# CurrentSensor.net
KiCad netlist of a schematic drawn in Altium Designer
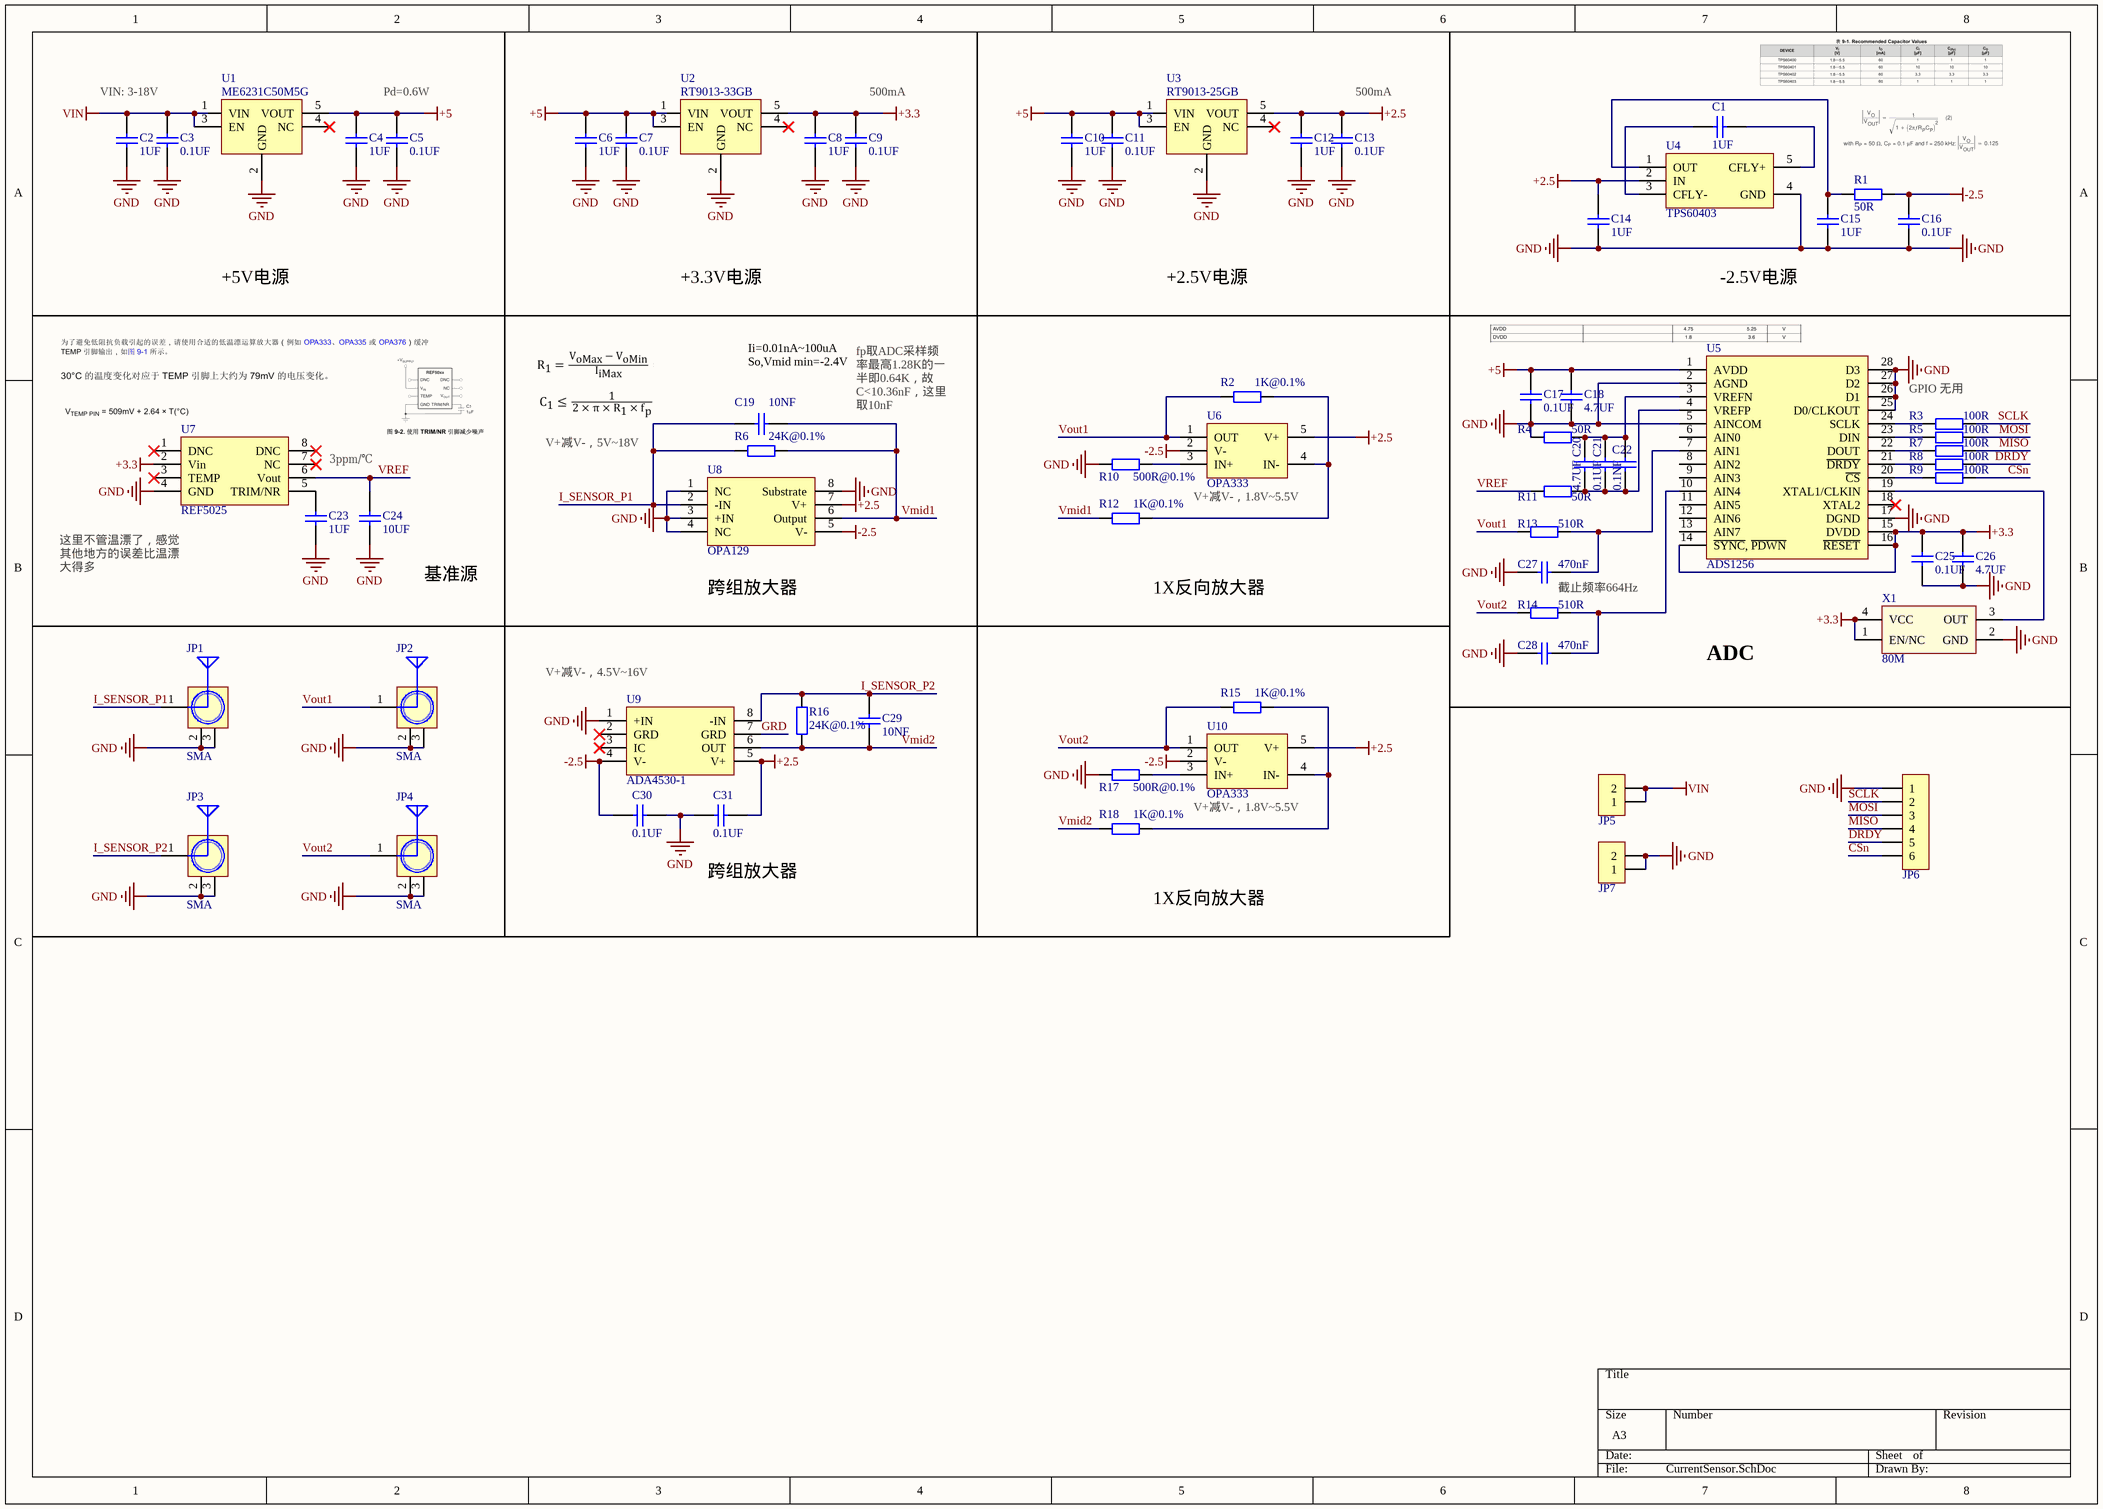
[diagram p0: CurrentSensor.SchDoc]

(export (version "E")
  (design (tool "Eeschema 10.0.6"))
  (components
    (comp (ref "C1")
      (value "1UF")
      (footprint "C0603_NS")
      (description "贴片电容/MLCC电容")
      (libsource (lib "阻容") (part "C"))
    )
    (comp (ref "C2")
      (value "1UF")
      (footprint "C0603_NS")
      (description "贴片电容/MLCC电容")
      (libsource (lib "阻容") (part "C"))
    )
    (comp (ref "C3")
      (value "0.1UF")
      (footprint "C0402_NS")
      (description "贴片电容/MLCC电容")
      (libsource (lib "阻容") (part "C"))
    )
    (comp (ref "C4")
      (value "1UF")
      (footprint "C0603_NS")
      (description "贴片电容/MLCC电容")
      (libsource (lib "阻容") (part "C"))
    )
    (comp (ref "C5")
      (value "0.1UF")
      (footprint "C0402_NS")
      (description "贴片电容/MLCC电容")
      (libsource (lib "阻容") (part "C"))
    )
    (comp (ref "C6")
      (value "1UF")
      (footprint "C0603_NS")
      (description "贴片电容/MLCC电容")
      (libsource (lib "阻容") (part "C"))
    )
    (comp (ref "C7")
      (value "0.1UF")
      (footprint "C0402_NS")
      (description "贴片电容/MLCC电容")
      (libsource (lib "阻容") (part "C"))
    )
    (comp (ref "C8")
      (value "1UF")
      (footprint "C0603_NS")
      (description "贴片电容/MLCC电容")
      (libsource (lib "阻容") (part "C"))
    )
    (comp (ref "C9")
      (value "0.1UF")
      (footprint "C0402_NS")
      (description "贴片电容/MLCC电容")
      (libsource (lib "阻容") (part "C"))
    )
    (comp (ref "C10")
      (value "1UF")
      (footprint "C0603_NS")
      (description "贴片电容/MLCC电容")
      (libsource (lib "阻容") (part "C"))
    )
    (comp (ref "C11")
      (value "0.1UF")
      (footprint "C0402_NS")
      (description "贴片电容/MLCC电容")
      (libsource (lib "阻容") (part "C"))
    )
    (comp (ref "C12")
      (value "1UF")
      (footprint "C0603_NS")
      (description "贴片电容/MLCC电容")
      (libsource (lib "阻容") (part "C"))
    )
    (comp (ref "C13")
      (value "0.1UF")
      (footprint "C0402_NS")
      (description "贴片电容/MLCC电容")
      (libsource (lib "阻容") (part "C"))
    )
    (comp (ref "C14")
      (value "1UF")
      (footprint "C0603_NS")
      (description "贴片电容/MLCC电容")
      (libsource (lib "阻容") (part "C"))
    )
    (comp (ref "C15")
      (value "1UF")
      (footprint "C0603_NS")
      (description "贴片电容/MLCC电容")
      (libsource (lib "阻容") (part "C"))
    )
    (comp (ref "C16")
      (value "0.1UF")
      (footprint "C0603_NS")
      (description "贴片电容/MLCC电容")
      (libsource (lib "阻容") (part "C"))
    )
    (comp (ref "C17")
      (value "0.1UF")
      (footprint "C0402_NS")
      (description "贴片电容/MLCC电容")
      (libsource (lib "阻容") (part "C"))
    )
    (comp (ref "C18")
      (value "4.7UF")
      (footprint "C0603_NS")
      (description "贴片电容/MLCC电容")
      (libsource (lib "阻容") (part "C"))
    )
    (comp (ref "C19")
      (value "10NF")
      (footprint "C0805_NS")
      (description "贴片电容/MLCC电容")
      (libsource (lib "阻容") (part "C"))
    )
    (comp (ref "C20")
      (value "4.7UF")
      (footprint "C0603_NS")
      (description "贴片电容/MLCC电容")
      (libsource (lib "阻容") (part "C"))
    )
    (comp (ref "C21")
      (value "0.1UF")
      (footprint "C0402_NS")
      (description "贴片电容/MLCC电容")
      (libsource (lib "阻容") (part "C"))
    )
    (comp (ref "C22")
      (value "0.1NF")
      (footprint "C0402_NS")
      (description "贴片电容/MLCC电容")
      (libsource (lib "阻容") (part "C"))
    )
    (comp (ref "C23")
      (value "1UF")
      (footprint "C0603_NS")
      (description "贴片电容/MLCC电容")
      (libsource (lib "阻容") (part "C"))
    )
    (comp (ref "C24")
      (value "10UF")
      (footprint "C0805_NS")
      (description "贴片电容/MLCC电容")
      (libsource (lib "阻容") (part "C"))
    )
    (comp (ref "C25")
      (value "0.1UF")
      (footprint "C0402_NS")
      (description "贴片电容/MLCC电容")
      (libsource (lib "阻容") (part "C"))
    )
    (comp (ref "C26")
      (value "4.7UF")
      (footprint "C0603_NS")
      (description "贴片电容/MLCC电容")
      (libsource (lib "阻容") (part "C"))
    )
    (comp (ref "C27")
      (value "470nF")
      (footprint "C0402_NS")
      (description "贴片电容/MLCC电容")
      (libsource (lib "阻容") (part "C"))
    )
    (comp (ref "C28")
      (value "470nF")
      (footprint "C0402_NS")
      (description "贴片电容/MLCC电容")
      (libsource (lib "阻容") (part "C"))
    )
    (comp (ref "C29")
      (value "10NF")
      (footprint "C0805_NS")
      (description "贴片电容/MLCC电容")
      (libsource (lib "阻容") (part "C"))
    )
    (comp (ref "C30")
      (value "0.1UF")
      (footprint "C0603_NS")
      (description "贴片电容/MLCC电容")
      (libsource (lib "阻容") (part "C"))
    )
    (comp (ref "C31")
      (value "0.1UF")
      (footprint "C0603_NS")
      (description "贴片电容/MLCC电容")
      (libsource (lib "阻容") (part "C"))
    )
    (comp (ref "JP1")
      (value "SMA")
      (footprint "SMA-KE")
      (description "SMA-2.4G射频天线接口")
      (libsource (lib "接口") (part "SMA"))
    )
    (comp (ref "JP2")
      (value "SMA")
      (footprint "SMA-KE")
      (description "SMA-2.4G射频天线接口")
      (libsource (lib "接口") (part "SMA"))
    )
    (comp (ref "JP3")
      (value "SMA")
      (footprint "SMA-KE")
      (description "SMA-2.4G射频天线接口")
      (libsource (lib "接口") (part "SMA"))
    )
    (comp (ref "JP4")
      (value "SMA")
      (footprint "SMA-KE")
      (description "SMA-2.4G射频天线接口")
      (libsource (lib "接口") (part "SMA"))
    )
    (comp (ref "JP5")
      (value "HDR-1X2")
      (footprint "HDR2.54-LI-2P")
      (description "2P接插件")
      (libsource (lib "2.54mm连接器") (part "Header 2"))
    )
    (comp (ref "JP6")
      (value "HDR-1X6")
      (footprint "HDR2.54-LI-6P")
      (description "6P接插件")
      (libsource (lib "2.54mm连接器") (part "Header 6"))
    )
    (comp (ref "JP7")
      (value "HDR-1X2")
      (footprint "HDR2.54-LI-2P")
      (description "2P接插件")
      (libsource (lib "2.54mm连接器") (part "Header 2"))
    )
    (comp (ref "R1")
      (value "50R")
      (footprint "R0603_NS")
      (description "贴片电阻")
      (libsource (lib "阻容") (part "R"))
    )
    (comp (ref "R2")
      (value "1K@0.1%")
      (footprint "R0805_NS")
      (description "贴片电阻")
      (libsource (lib "阻容") (part "R"))
    )
    (comp (ref "R3")
      (value "100R")
      (footprint "R0402_NS")
      (description "贴片电阻")
      (libsource (lib "阻容") (part "R"))
    )
    (comp (ref "R4")
      (value "50R")
      (footprint "R0402_NS")
      (description "贴片电阻")
      (libsource (lib "阻容") (part "R"))
    )
    (comp (ref "R5")
      (value "100R")
      (footprint "R0402_NS")
      (description "贴片电阻")
      (libsource (lib "阻容") (part "R"))
    )
    (comp (ref "R6")
      (value "24K@0.1%")
      (footprint "R0805_NS")
      (description "贴片电阻")
      (libsource (lib "阻容") (part "R"))
    )
    (comp (ref "R7")
      (value "100R")
      (footprint "R0402_NS")
      (description "贴片电阻")
      (libsource (lib "阻容") (part "R"))
    )
    (comp (ref "R8")
      (value "100R")
      (footprint "R0402_NS")
      (description "贴片电阻")
      (libsource (lib "阻容") (part "R"))
    )
    (comp (ref "R9")
      (value "100R")
      (footprint "R0402_NS")
      (description "贴片电阻")
      (libsource (lib "阻容") (part "R"))
    )
    (comp (ref "R10")
      (value "500R@0.1%")
      (footprint "R0805_NS")
      (description "贴片电阻")
      (libsource (lib "阻容") (part "R"))
    )
    (comp (ref "R11")
      (value "50R")
      (footprint "R0402_NS")
      (description "贴片电阻")
      (libsource (lib "阻容") (part "R"))
    )
    (comp (ref "R12")
      (value "1K@0.1%")
      (footprint "R0805_NS")
      (description "贴片电阻")
      (libsource (lib "阻容") (part "R"))
    )
    (comp (ref "R13")
      (value "510R")
      (footprint "R0402_NS")
      (description "贴片电阻")
      (libsource (lib "阻容") (part "R"))
    )
    (comp (ref "R14")
      (value "510R")
      (footprint "R0402_NS")
      (description "贴片电阻")
      (libsource (lib "阻容") (part "R"))
    )
    (comp (ref "R15")
      (value "1K@0.1%")
      (footprint "R0805_NS")
      (description "贴片电阻")
      (libsource (lib "阻容") (part "R"))
    )
    (comp (ref "R16")
      (value "24K@0.1%")
      (footprint "R0805_NS")
      (description "贴片电阻")
      (libsource (lib "阻容") (part "R"))
    )
    (comp (ref "R17")
      (value "500R@0.1%")
      (footprint "R0805_NS")
      (description "贴片电阻")
      (libsource (lib "阻容") (part "R"))
    )
    (comp (ref "R18")
      (value "1K@0.1%")
      (footprint "R0805_NS")
      (description "贴片电阻")
      (libsource (lib "阻容") (part "R"))
    )
    (comp (ref "U1")
      (value "ME6231C50M5G")
      (footprint "SOT23-5_L3.0_W1.7_P0.95")
      (description "500mA 低压差, 低噪声, 超快速线性稳压器")
      (libsource (lib "LDO") (part "RT9013-33GB"))
    )
    (comp (ref "U2")
      (value "RT9013-33GB")
      (footprint "SOT23-5_L3.0_W1.7_P0.95")
      (description "500mA 低压差, 低噪声, 超快速线性稳压器")
      (libsource (lib "LDO") (part "RT9013-33GB"))
    )
    (comp (ref "U3")
      (value "RT9013-25GB")
      (footprint "SOT23-5_L3.0_W1.7_P0.95")
      (description "500mA 低压差, 低噪声, 超快速线性稳压器")
      (libsource (lib "LDO") (part "RT9013-33GB"))
    )
    (comp (ref "U4")
      (value "TPS60403")
      (footprint "SOT23-5_L3.0_W1.7_P0.95")
      (description "具有固定 250kHz 操作的 60mA 电荷泵电压反向器")
      (libsource (lib "电源IC") (part "TPS60403"))
    )
    (comp (ref "U5")
      (value "ADS1256")
      (footprint "SSOP28_L10.2_W7.8_P0.65")
      (description "适用于工厂自动化和过程控制且具有 PGA 的 24 位、30kSPS、8 通道 Δ-Σ ADC")
      (libsource (lib "其他") (part "ADS1256"))
    )
    (comp (ref "U6")
      (value "OPA333")
      (footprint "SOT23-5_L3.0_W1.7_P0.95")
      (description "1.8V、17µA、微功耗、精密、零漂移 CMOS 运算放大器")
      (libsource (lib "运放") (part "OPA333"))
    )
    (comp (ref "U7")
      (value "REF5025")
      (footprint "SOP8_L6.0_W5.0_P1.27")
      (description "2.5V、3µVpp/V 噪声、3ppm/°C 温漂、精密串联电压基准")
      (libsource (lib "运放") (part "REF50XX"))
    )
    (comp (ref "U8")
      (value "OPA129")
      (footprint "SOP8_L6.0_W5.0_P1.27")
      (description "超低偏置电流差动运算放大器")
      (libsource (lib "运放") (part "OPA129"))
    )
    (comp (ref "U9")
      (value "ADA4530-1")
      (footprint "SOP8_L6.0_W5.0_P1.27")
      (description "微微安输入偏置电流静电计放大器")
      (libsource (lib "运放") (part "ADA4530-1"))
    )
    (comp (ref "U10")
      (value "OPA333")
      (footprint "SOT23-5_L3.0_W1.7_P0.95")
      (description "1.8V、17µA、微功耗、精密、零漂移 CMOS 运算放大器")
      (libsource (lib "运放") (part "OPA333"))
    )
    (comp (ref "X1")
      (value "80M")
      (footprint "OSC-3225-4P")
      (description "4脚有源晶振(振荡器)")
      (libsource (lib "晶振") (part "XTAL-ACT-4P"))
    )
  )
  (nets
    (net (code "1") (name "+2.5") (class "Default")
      (node (ref "C12") (pin "2") (pinfunction "2_2") (pintype "passive"))
      (node (ref "C13") (pin "2") (pinfunction "2_2") (pintype "passive"))
      (node (ref "C14") (pin "2") (pinfunction "2_2") (pintype "passive"))
      (node (ref "C31") (pin "2") (pinfunction "2_2") (pintype "passive"))
      (node (ref "U10") (pin "5") (pinfunction "V+_5") (pintype "passive"))
      (node (ref "U3") (pin "5") (pinfunction "VOUT_5") (pintype "passive"))
      (node (ref "U4") (pin "2") (pinfunction "IN_2") (pintype "passive"))
      (node (ref "U6") (pin "5") (pinfunction "V+_5") (pintype "passive"))
      (node (ref "U8") (pin "7") (pinfunction "V+_7") (pintype "passive"))
      (node (ref "U9") (pin "5") (pinfunction "V+_5") (pintype "passive"))
    )
    (net (code "2") (name "+3.3") (class "Default")
      (node (ref "C25") (pin "2") (pinfunction "2_2") (pintype "passive"))
      (node (ref "C26") (pin "1") (pinfunction "1_1") (pintype "passive"))
      (node (ref "C8") (pin "2") (pinfunction "2_2") (pintype "passive"))
      (node (ref "C9") (pin "2") (pinfunction "2_2") (pintype "passive"))
      (node (ref "U2") (pin "5") (pinfunction "VOUT_5") (pintype "passive"))
      (node (ref "U5") (pin "14") (pinfunction "~{SYNC},_~{PDWN}_14") (pintype "passive"))
      (node (ref "U5") (pin "15") (pinfunction "DVDD_15") (pintype "passive"))
      (node (ref "U5") (pin "16") (pinfunction "~{RESET}_16") (pintype "passive"))
      (node (ref "U7") (pin "2") (pinfunction "Vin_2") (pintype "passive"))
      (node (ref "X1") (pin "1") (pinfunction "EN/NC_1") (pintype "passive"))
      (node (ref "X1") (pin "4") (pinfunction "VCC_4") (pintype "passive"))
    )
    (net (code "3") (name "+5") (class "Default")
      (node (ref "C10") (pin "2") (pinfunction "2_2") (pintype "passive"))
      (node (ref "C11") (pin "2") (pinfunction "2_2") (pintype "passive"))
      (node (ref "C17") (pin "2") (pinfunction "2_2") (pintype "passive"))
      (node (ref "C18") (pin "1") (pinfunction "1_1") (pintype "passive"))
      (node (ref "C4") (pin "2") (pinfunction "2_2") (pintype "passive"))
      (node (ref "C5") (pin "2") (pinfunction "2_2") (pintype "passive"))
      (node (ref "C6") (pin "2") (pinfunction "2_2") (pintype "passive"))
      (node (ref "C7") (pin "2") (pinfunction "2_2") (pintype "passive"))
      (node (ref "U1") (pin "5") (pinfunction "VOUT_5") (pintype "passive"))
      (node (ref "U2") (pin "1") (pinfunction "VIN_1") (pintype "passive"))
      (node (ref "U2") (pin "3") (pinfunction "EN_3") (pintype "passive"))
      (node (ref "U3") (pin "1") (pinfunction "VIN_1") (pintype "passive"))
      (node (ref "U3") (pin "3") (pinfunction "EN_3") (pintype "passive"))
      (node (ref "U5") (pin "1") (pinfunction "AVDD_1") (pintype "passive"))
    )
    (net (code "4") (name "-2.5") (class "Default")
      (node (ref "C16") (pin "2") (pinfunction "2_2") (pintype "passive"))
      (node (ref "C30") (pin "1") (pinfunction "1_1") (pintype "passive"))
      (node (ref "R1") (pin "2") (pinfunction "2_2") (pintype "passive"))
      (node (ref "U10") (pin "2") (pinfunction "V-_2") (pintype "passive"))
      (node (ref "U6") (pin "2") (pinfunction "V-_2") (pintype "passive"))
      (node (ref "U8") (pin "5") (pinfunction "V-_5") (pintype "passive"))
      (node (ref "U9") (pin "4") (pinfunction "V-_4") (pintype "passive"))
    )
    (net (code "5") (name "/CSn") (class "Default")
      (node (ref "JP6") (pin "6") (pinfunction "6_6") (pintype "passive"))
      (node (ref "R9") (pin "1") (pinfunction "1_1") (pintype "passive"))
    )
    (net (code "6") (name "/DRDY") (class "Default")
      (node (ref "JP6") (pin "5") (pinfunction "5_5") (pintype "passive"))
      (node (ref "R8") (pin "1") (pinfunction "1_1") (pintype "passive"))
    )
    (net (code "7") (name "/GRD") (class "Default")
      (node (ref "U9") (pin "7") (pinfunction "GRD_7") (pintype "passive"))
    )
    (net (code "8") (name "/I_SENSOR_P1") (class "Default")
      (node (ref "C19") (pin "1") (pinfunction "1_1") (pintype "passive"))
      (node (ref "JP1") (pin "1") (pinfunction "ANT_1") (pintype "passive"))
      (node (ref "R6") (pin "2") (pinfunction "2_2") (pintype "passive"))
      (node (ref "U8") (pin "2") (pinfunction "-IN_2") (pintype "passive"))
    )
    (net (code "9") (name "/I_SENSOR_P2") (class "Default")
      (node (ref "C29") (pin "2") (pinfunction "2_2") (pintype "passive"))
      (node (ref "JP3") (pin "1") (pinfunction "ANT_1") (pintype "passive"))
      (node (ref "R16") (pin "1") (pinfunction "1_1") (pintype "passive"))
      (node (ref "U9") (pin "8") (pinfunction "-IN_8") (pintype "passive"))
    )
    (net (code "10") (name "/MISO") (class "Default")
      (node (ref "JP6") (pin "4") (pinfunction "4_4") (pintype "passive"))
      (node (ref "R7") (pin "1") (pinfunction "1_1") (pintype "passive"))
    )
    (net (code "11") (name "/MOSI") (class "Default")
      (node (ref "JP6") (pin "3") (pinfunction "3_3") (pintype "passive"))
      (node (ref "R5") (pin "1") (pinfunction "1_1") (pintype "passive"))
    )
    (net (code "12") (name "/SCLK") (class "Default")
      (node (ref "JP6") (pin "2") (pinfunction "2_2") (pintype "passive"))
      (node (ref "R3") (pin "1") (pinfunction "1_1") (pintype "passive"))
    )
    (net (code "13") (name "/VREF") (class "Default")
      (node (ref "C24") (pin "1") (pinfunction "1_1") (pintype "passive"))
      (node (ref "R11") (pin "2") (pinfunction "2_2") (pintype "passive"))
      (node (ref "U7") (pin "6") (pinfunction "Vout_6") (pintype "passive"))
    )
    (net (code "14") (name "/Vmid1") (class "Default")
      (node (ref "C19") (pin "2") (pinfunction "2_2") (pintype "passive"))
      (node (ref "R12") (pin "2") (pinfunction "2_2") (pintype "passive"))
      (node (ref "R6") (pin "1") (pinfunction "1_1") (pintype "passive"))
      (node (ref "U8") (pin "6") (pinfunction "Output_6") (pintype "passive"))
    )
    (net (code "15") (name "/Vmid2") (class "Default")
      (node (ref "C29") (pin "1") (pinfunction "1_1") (pintype "passive"))
      (node (ref "R16") (pin "2") (pinfunction "2_2") (pintype "passive"))
      (node (ref "R18") (pin "2") (pinfunction "2_2") (pintype "passive"))
      (node (ref "U9") (pin "6") (pinfunction "OUT_6") (pintype "passive"))
    )
    (net (code "16") (name "/Vout1") (class "Default")
      (node (ref "JP2") (pin "1") (pinfunction "ANT_1") (pintype "passive"))
      (node (ref "R13") (pin "2") (pinfunction "2_2") (pintype "passive"))
      (node (ref "R2") (pin "2") (pinfunction "2_2") (pintype "passive"))
      (node (ref "U6") (pin "1") (pinfunction "OUT_1") (pintype "passive"))
    )
    (net (code "17") (name "/Vout2") (class "Default")
      (node (ref "JP4") (pin "1") (pinfunction "ANT_1") (pintype "passive"))
      (node (ref "R14") (pin "2") (pinfunction "2_2") (pintype "passive"))
      (node (ref "R15") (pin "2") (pinfunction "2_2") (pintype "passive"))
      (node (ref "U10") (pin "1") (pinfunction "OUT_1") (pintype "passive"))
    )
    (net (code "18") (name "GND") (class "Default")
      (node (ref "C10") (pin "1") (pinfunction "1_1") (pintype "passive"))
      (node (ref "C11") (pin "1") (pinfunction "1_1") (pintype "passive"))
      (node (ref "C12") (pin "1") (pinfunction "1_1") (pintype "passive"))
      (node (ref "C13") (pin "1") (pinfunction "1_1") (pintype "passive"))
      (node (ref "C14") (pin "1") (pinfunction "1_1") (pintype "passive"))
      (node (ref "C15") (pin "1") (pinfunction "1_1") (pintype "passive"))
      (node (ref "C16") (pin "1") (pinfunction "1_1") (pintype "passive"))
      (node (ref "C17") (pin "1") (pinfunction "1_1") (pintype "passive"))
      (node (ref "C18") (pin "2") (pinfunction "2_2") (pintype "passive"))
      (node (ref "C2") (pin "1") (pinfunction "1_1") (pintype "passive"))
      (node (ref "C23") (pin "1") (pinfunction "1_1") (pintype "passive"))
      (node (ref "C24") (pin "2") (pinfunction "2_2") (pintype "passive"))
      (node (ref "C25") (pin "1") (pinfunction "1_1") (pintype "passive"))
      (node (ref "C26") (pin "2") (pinfunction "2_2") (pintype "passive"))
      (node (ref "C27") (pin "1") (pinfunction "1_1") (pintype "passive"))
      (node (ref "C28") (pin "1") (pinfunction "1_1") (pintype "passive"))
      (node (ref "C3") (pin "1") (pinfunction "1_1") (pintype "passive"))
      (node (ref "C30") (pin "2") (pinfunction "2_2") (pintype "passive"))
      (node (ref "C31") (pin "1") (pinfunction "1_1") (pintype "passive"))
      (node (ref "C4") (pin "1") (pinfunction "1_1") (pintype "passive"))
      (node (ref "C5") (pin "1") (pinfunction "1_1") (pintype "passive"))
      (node (ref "C6") (pin "1") (pinfunction "1_1") (pintype "passive"))
      (node (ref "C7") (pin "1") (pinfunction "1_1") (pintype "passive"))
      (node (ref "C8") (pin "1") (pinfunction "1_1") (pintype "passive"))
      (node (ref "C9") (pin "1") (pinfunction "1_1") (pintype "passive"))
      (node (ref "JP1") (pin "2") (pinfunction "GND_2") (pintype "passive"))
      (node (ref "JP1") (pin "3") (pinfunction "GND_3") (pintype "passive"))
      (node (ref "JP2") (pin "2") (pinfunction "GND_2") (pintype "passive"))
      (node (ref "JP2") (pin "3") (pinfunction "GND_3") (pintype "passive"))
      (node (ref "JP3") (pin "2") (pinfunction "GND_2") (pintype "passive"))
      (node (ref "JP3") (pin "3") (pinfunction "GND_3") (pintype "passive"))
      (node (ref "JP4") (pin "2") (pinfunction "GND_2") (pintype "passive"))
      (node (ref "JP4") (pin "3") (pinfunction "GND_3") (pintype "passive"))
      (node (ref "JP6") (pin "1") (pinfunction "1_1") (pintype "passive"))
      (node (ref "JP7") (pin "1") (pinfunction "1_1") (pintype "passive"))
      (node (ref "JP7") (pin "2") (pinfunction "2_2") (pintype "passive"))
      (node (ref "R10") (pin "2") (pinfunction "2_2") (pintype "passive"))
      (node (ref "R17") (pin "2") (pinfunction "2_2") (pintype "passive"))
      (node (ref "R4") (pin "2") (pinfunction "2_2") (pintype "passive"))
      (node (ref "U1") (pin "2") (pinfunction "GND_2") (pintype "passive"))
      (node (ref "U2") (pin "2") (pinfunction "GND_2") (pintype "passive"))
      (node (ref "U3") (pin "2") (pinfunction "GND_2") (pintype "passive"))
      (node (ref "U4") (pin "4") (pinfunction "GND_4") (pintype "passive"))
      (node (ref "U5") (pin "17") (pinfunction "DGND_17") (pintype "passive"))
      (node (ref "U5") (pin "2") (pinfunction "AGND_2") (pintype "passive"))
      (node (ref "U5") (pin "25") (pinfunction "D0/CLKOUT_25") (pintype "passive"))
      (node (ref "U5") (pin "26") (pinfunction "D1_26") (pintype "passive"))
      (node (ref "U5") (pin "27") (pinfunction "D2_27") (pintype "passive"))
      (node (ref "U5") (pin "28") (pinfunction "D3_28") (pintype "passive"))
      (node (ref "U5") (pin "5") (pinfunction "AINCOM_5") (pintype "passive"))
      (node (ref "U7") (pin "4") (pinfunction "GND_4") (pintype "passive"))
      (node (ref "U8") (pin "1") (pinfunction "NC_1") (pintype "passive"))
      (node (ref "U8") (pin "3") (pinfunction "+IN_3") (pintype "passive"))
      (node (ref "U8") (pin "4") (pinfunction "NC_4") (pintype "passive"))
      (node (ref "U8") (pin "8") (pinfunction "Substrate_8") (pintype "passive"))
      (node (ref "U9") (pin "1") (pinfunction "+IN_1") (pintype "passive"))
      (node (ref "X1") (pin "2") (pinfunction "GND_2") (pintype "passive"))
    )
    (net (code "19") (name "Net-(U4-CFLY+)") (class "Default")
      (node (ref "C1") (pin "1") (pinfunction "1_1") (pintype "passive"))
      (node (ref "U4") (pin "5") (pinfunction "CFLY+_5") (pintype "passive"))
    )
    (net (code "20") (name "Net-(U4-CFLY-)") (class "Default")
      (node (ref "C1") (pin "2") (pinfunction "2_2") (pintype "passive"))
      (node (ref "U4") (pin "3") (pinfunction "CFLY-_3") (pintype "passive"))
    )
    (net (code "21") (name "Net-(U4-OUT)") (class "Default")
      (node (ref "C15") (pin "2") (pinfunction "2_2") (pintype "passive"))
      (node (ref "R1") (pin "1") (pinfunction "1_1") (pintype "passive"))
      (node (ref "U4") (pin "1") (pinfunction "OUT_1") (pintype "passive"))
    )
    (net (code "22") (name "Net-(U5-AIN1)") (class "Default")
      (node (ref "C27") (pin "2") (pinfunction "2_2") (pintype "passive"))
      (node (ref "R13") (pin "1") (pinfunction "1_1") (pintype "passive"))
      (node (ref "U5") (pin "7") (pinfunction "AIN1_7") (pintype "passive"))
    )
    (net (code "23") (name "Net-(U5-AIN4)") (class "Default")
      (node (ref "C28") (pin "2") (pinfunction "2_2") (pintype "passive"))
      (node (ref "R14") (pin "1") (pinfunction "1_1") (pintype "passive"))
      (node (ref "U5") (pin "10") (pinfunction "AIN4_10") (pintype "passive"))
    )
    (net (code "24") (name "Net-(U5-DIN)") (class "Default")
      (node (ref "R5") (pin "2") (pinfunction "2_2") (pintype "passive"))
      (node (ref "U5") (pin "23") (pinfunction "DIN_23") (pintype "passive"))
    )
    (net (code "25") (name "Net-(U5-DOUT)") (class "Default")
      (node (ref "R7") (pin "2") (pinfunction "2_2") (pintype "passive"))
      (node (ref "U5") (pin "22") (pinfunction "DOUT_22") (pintype "passive"))
    )
    (net (code "26") (name "Net-(U5-SCLK)") (class "Default")
      (node (ref "R3") (pin "2") (pinfunction "2_2") (pintype "passive"))
      (node (ref "U5") (pin "24") (pinfunction "SCLK_24") (pintype "passive"))
    )
    (net (code "27") (name "Net-(U5-VREFN)") (class "Default")
      (node (ref "C20") (pin "1") (pinfunction "1_1") (pintype "passive"))
      (node (ref "C21") (pin "1") (pinfunction "1_1") (pintype "passive"))
      (node (ref "C22") (pin "1") (pinfunction "1_1") (pintype "passive"))
      (node (ref "R4") (pin "1") (pinfunction "1_1") (pintype "passive"))
      (node (ref "U5") (pin "3") (pinfunction "VREFN_3") (pintype "passive"))
    )
    (net (code "28") (name "Net-(U5-VREFP)") (class "Default")
      (node (ref "C20") (pin "2") (pinfunction "2_2") (pintype "passive"))
      (node (ref "C21") (pin "2") (pinfunction "2_2") (pintype "passive"))
      (node (ref "C22") (pin "2") (pinfunction "2_2") (pintype "passive"))
      (node (ref "R11") (pin "1") (pinfunction "1_1") (pintype "passive"))
      (node (ref "U5") (pin "4") (pinfunction "VREFP_4") (pintype "passive"))
    )
    (net (code "29") (name "Net-(U5-XTAL1{slash}CLKIN)") (class "Default")
      (node (ref "U5") (pin "19") (pinfunction "XTAL1/CLKIN_19") (pintype "passive"))
      (node (ref "X1") (pin "3") (pinfunction "OUT_3") (pintype "passive"))
    )
    (net (code "30") (name "Net-(U5-~{CS})") (class "Default")
      (node (ref "R9") (pin "2") (pinfunction "2_2") (pintype "passive"))
      (node (ref "U5") (pin "20") (pinfunction "~{CS}_20") (pintype "passive"))
    )
    (net (code "31") (name "Net-(U5-~{DRDY})") (class "Default")
      (node (ref "R8") (pin "2") (pinfunction "2_2") (pintype "passive"))
      (node (ref "U5") (pin "21") (pinfunction "~{DRDY}_21") (pintype "passive"))
    )
    (net (code "32") (name "Net-(U6-IN+)") (class "Default")
      (node (ref "R10") (pin "1") (pinfunction "1_1") (pintype "passive"))
      (node (ref "U6") (pin "3") (pinfunction "IN+_3") (pintype "passive"))
    )
    (net (code "33") (name "Net-(U6-IN-)") (class "Default")
      (node (ref "R12") (pin "1") (pinfunction "1_1") (pintype "passive"))
      (node (ref "R2") (pin "1") (pinfunction "1_1") (pintype "passive"))
      (node (ref "U6") (pin "4") (pinfunction "IN-_4") (pintype "passive"))
    )
    (net (code "34") (name "Net-(U7-TRIM{slash}NR)") (class "Default")
      (node (ref "C23") (pin "2") (pinfunction "2_2") (pintype "passive"))
      (node (ref "U7") (pin "5") (pinfunction "TRIM/NR_5") (pintype "passive"))
    )
    (net (code "35") (name "Net-(U10-IN+)") (class "Default")
      (node (ref "R17") (pin "1") (pinfunction "1_1") (pintype "passive"))
      (node (ref "U10") (pin "3") (pinfunction "IN+_3") (pintype "passive"))
    )
    (net (code "36") (name "Net-(U10-IN-)") (class "Default")
      (node (ref "R15") (pin "1") (pinfunction "1_1") (pintype "passive"))
      (node (ref "R18") (pin "1") (pinfunction "1_1") (pintype "passive"))
      (node (ref "U10") (pin "4") (pinfunction "IN-_4") (pintype "passive"))
    )
    (net (code "37") (name "VIN") (class "Default")
      (node (ref "C2") (pin "2") (pinfunction "2_2") (pintype "passive"))
      (node (ref "C3") (pin "2") (pinfunction "2_2") (pintype "passive"))
      (node (ref "JP5") (pin "1") (pinfunction "1_1") (pintype "passive"))
      (node (ref "JP5") (pin "2") (pinfunction "2_2") (pintype "passive"))
      (node (ref "U1") (pin "1") (pinfunction "VIN_1") (pintype "passive"))
      (node (ref "U1") (pin "3") (pinfunction "EN_3") (pintype "passive"))
    )
    (net (code "38") (name "unconnected-(U1-NC-Pad4)") (class "Default")
      (node (ref "U1") (pin "4") (pinfunction "NC_4") (pintype "passive+no_connect"))
    )
    (net (code "39") (name "unconnected-(U2-NC-Pad4)") (class "Default")
      (node (ref "U2") (pin "4") (pinfunction "NC_4") (pintype "passive+no_connect"))
    )
    (net (code "40") (name "unconnected-(U3-NC-Pad4)") (class "Default")
      (node (ref "U3") (pin "4") (pinfunction "NC_4") (pintype "passive+no_connect"))
    )
    (net (code "41") (name "unconnected-(U5-AIN0-Pad6)") (class "Default")
      (node (ref "U5") (pin "6") (pinfunction "AIN0_6") (pintype "passive"))
    )
    (net (code "42") (name "unconnected-(U5-AIN2-Pad8)") (class "Default")
      (node (ref "U5") (pin "8") (pinfunction "AIN2_8") (pintype "passive"))
    )
    (net (code "43") (name "unconnected-(U5-AIN3-Pad9)") (class "Default")
      (node (ref "U5") (pin "9") (pinfunction "AIN3_9") (pintype "passive"))
    )
    (net (code "44") (name "unconnected-(U5-AIN5-Pad11)") (class "Default")
      (node (ref "U5") (pin "11") (pinfunction "AIN5_11") (pintype "passive"))
    )
    (net (code "45") (name "unconnected-(U5-AIN6-Pad12)") (class "Default")
      (node (ref "U5") (pin "12") (pinfunction "AIN6_12") (pintype "passive"))
    )
    (net (code "46") (name "unconnected-(U5-AIN7-Pad13)") (class "Default")
      (node (ref "U5") (pin "13") (pinfunction "AIN7_13") (pintype "passive"))
    )
    (net (code "47") (name "unconnected-(U5-XTAL2-Pad18)") (class "Default")
      (node (ref "U5") (pin "18") (pinfunction "XTAL2_18") (pintype "passive+no_connect"))
    )
    (net (code "48") (name "unconnected-(U7-DNC-Pad1)") (class "Default")
      (node (ref "U7") (pin "1") (pinfunction "DNC_1") (pintype "passive+no_connect"))
    )
    (net (code "49") (name "unconnected-(U7-DNC-Pad8)") (class "Default")
      (node (ref "U7") (pin "8") (pinfunction "DNC_8") (pintype "passive+no_connect"))
    )
    (net (code "50") (name "unconnected-(U7-NC-Pad7)") (class "Default")
      (node (ref "U7") (pin "7") (pinfunction "NC_7") (pintype "passive+no_connect"))
    )
    (net (code "51") (name "unconnected-(U7-TEMP-Pad3)") (class "Default")
      (node (ref "U7") (pin "3") (pinfunction "TEMP_3") (pintype "passive+no_connect"))
    )
    (net (code "52") (name "unconnected-(U9-GRD-Pad2)") (class "Default")
      (node (ref "U9") (pin "2") (pinfunction "GRD_2") (pintype "passive+no_connect"))
    )
    (net (code "53") (name "unconnected-(U9-IC-Pad3)") (class "Default")
      (node (ref "U9") (pin "3") (pinfunction "IC_3") (pintype "passive+no_connect"))
    )
  )
)
